# Morpheus_LDO.net
KiCad netlist of a schematic drawn in Altium Designer
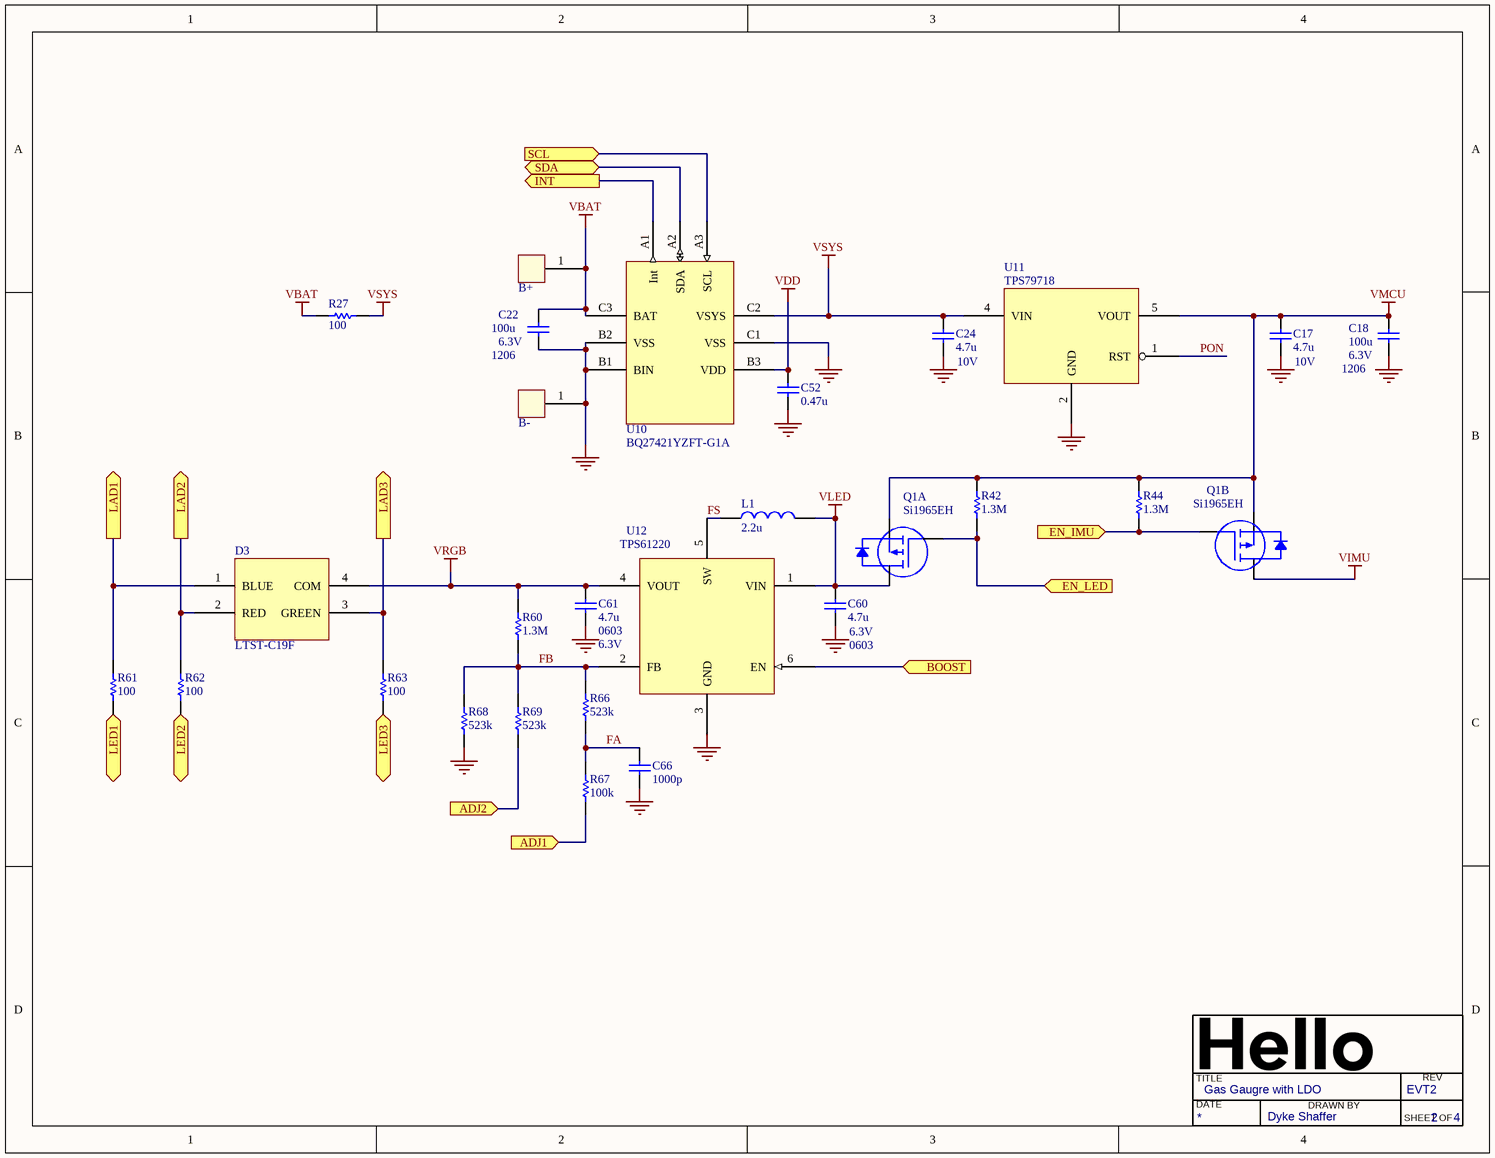
[diagram p0: Morpheus_LDO.SchDoc]

(export (version "E")
  (design (tool "Eeschema 10.0.6"))
  (components
    (comp (ref "B+")
      (value "5016")
      (footprint "TP0875x050")
      (description "Single-pad test point")
      (libsource (lib "Mopd") (part "5016"))
    )
    (comp (ref "B-")
      (value "5016")
      (footprint "TP0875x050")
      (description "Single-pad test point")
      (libsource (lib "Mopd") (part "5016"))
    )
    (comp (ref "C17")
      (value "4.7u")
      (footprint "CAP0402")
      (description "Chip capacitor")
      (fields (field (name "TOLERANCE") "10%") (field (name "VOLTAGE") "10V"))
      (libsource (lib "Hello") (part "C_4.7u_10_10_JB_0402"))
    )
    (comp (ref "C18")
      (value "100u")
      (footprint "CAP1206")
      (description "Chip capacitor")
      (fields (field (name "SIZE") "1206") (field (name "TOLERANCE") "20%") (field (name "VOLTAGE") "6.3V"))
      (libsource (lib "Hello") (part "C_100u_20_6.3_X5R_1206"))
    )
    (comp (ref "C22")
      (value "100u")
      (footprint "CAP1206")
      (description "Chip capacitor")
      (fields (field (name "SIZE") "1206") (field (name "TOLERANCE") "20%") (field (name "VOLTAGE") "6.3V"))
      (libsource (lib "Hello") (part "C_100u_20_6.3_X5R_1206"))
    )
    (comp (ref "C24")
      (value "4.7u")
      (footprint "CAP0402")
      (description "Chip capacitor")
      (fields (field (name "TOLERANCE") "10%") (field (name "VOLTAGE") "10V"))
      (libsource (lib "Hello") (part "C_4.7u_10_10_JB_0402"))
    )
    (comp (ref "C52")
      (value "0.47u")
      (footprint "CAP0402")
      (description "Chip capacitor")
      (fields (field (name "TOLERANCE") "10%") (field (name "VOLTAGE") "10V"))
      (libsource (lib "Hello") (part "C_0.47u_10_10_X5R_0402"))
    )
    (comp (ref "C60")
      (value "4.7u")
      (footprint "CAP0603")
      (description "Chip capacitor")
      (fields (field (name "SIZE") "0603") (field (name "TOLERANCE") "20%") (field (name "VOLTAGE") "6.3V"))
      (libsource (lib "Hello") (part "C_4.7u_20_6.3_X5R_0603"))
    )
    (comp (ref "C61")
      (value "4.7u")
      (footprint "CAP0603")
      (description "Chip capacitor")
      (fields (field (name "SIZE") "0603") (field (name "TOLERANCE") "20%") (field (name "VOLTAGE") "6.3V"))
      (libsource (lib "Hello") (part "C_4.7u_20_6.3_X5R_0603"))
    )
    (comp (ref "C66")
      (value "1000p")
      (footprint "CAP0402")
      (description "Chip capacitor")
      (fields (field (name "TOLERANCE") "10%") (field (name "VOLTAGE") "50V"))
      (libsource (lib "Hello") (part "C_1000p_10_50_X7R_0402"))
    )
    (comp (ref "D3")
      (value "LTST-C19F")
      (footprint "DFN165X210X160X80-4N")
      (description "RGB LED Array")
      (libsource (lib "dykes") (part "LTST-C19F"))
    )
    (comp (ref "L1")
      (value "2.2u")
      (footprint "IND_1206")
      (description "SMD power inductor, 2.2uH")
      (fields (field (name "TOLERANCE") "20%"))
      (libsource (lib "Hello") (part "L_2.2u_1206"))
    )
    (comp (ref "Q1")
      (value "Si1965EH")
      (footprint "SC-70-6")
      (description "Vishay Dual P-Channel MOSFET 1.8v drive 20V 1A")
      (libsource (lib "Hello") (part "Si1965EH"))
    )
    (comp (ref "R27")
      (value "100")
      (footprint "RES0402")
      (description "Chip Resistor")
      (fields (field (name "TOLERANCE") "1 %") (field (name "POWER") "0.1 W"))
      (libsource (lib "Hello") (part "R_100_1_0.1_0402"))
    )
    (comp (ref "R42")
      (value "1.3M")
      (footprint "RES0402")
      (description "Chip Resistor")
      (fields (field (name "TOLERANCE") "5 %") (field (name "POWER") "0.1 W"))
      (libsource (lib "Hello") (part "R_1.3M_5_0.1_0402_1"))
    )
    (comp (ref "R44")
      (value "1.3M")
      (footprint "RES0402")
      (description "Chip Resistor")
      (fields (field (name "TOLERANCE") "5 %") (field (name "POWER") "0.1 W"))
      (libsource (lib "Hello") (part "R_1.3M_5_0.1_0402_1"))
    )
    (comp (ref "R60")
      (value "1.3M")
      (footprint "RES0402")
      (description "Chip Resistor")
      (fields (field (name "TOLERANCE") "5 %") (field (name "POWER") "0.1 W"))
      (libsource (lib "Hello") (part "R_1.3M_5_0.1_0402_1"))
    )
    (comp (ref "R61")
      (value "100")
      (footprint "RES0402")
      (description "Chip Resistor")
      (fields (field (name "TOLERANCE") "1 %") (field (name "POWER") "0.1 W"))
      (libsource (lib "Hello") (part "R_100_1_0.1_0402"))
    )
    (comp (ref "R62")
      (value "100")
      (footprint "RES0402")
      (description "Chip Resistor")
      (fields (field (name "TOLERANCE") "1 %") (field (name "POWER") "0.1 W"))
      (libsource (lib "Hello") (part "R_100_1_0.1_0402"))
    )
    (comp (ref "R63")
      (value "100")
      (footprint "RES0402")
      (description "Chip Resistor")
      (fields (field (name "TOLERANCE") "1 %") (field (name "POWER") "0.1 W"))
      (libsource (lib "Hello") (part "R_100_1_0.1_0402"))
    )
    (comp (ref "R66")
      (value "523k")
      (footprint "RES0402")
      (description "Chip Resistor")
      (fields (field (name "TOLERANCE") "1 %") (field (name "POWER") "0.1 W"))
      (libsource (lib "Hello") (part "R_523k_1_0.1_0402"))
    )
    (comp (ref "R67")
      (value "100k")
      (footprint "RES0402")
      (description "Chip Resistor")
      (fields (field (name "TOLERANCE") "1 %") (field (name "POWER") "0.1 W"))
      (libsource (lib "Hello") (part "R_100k_1_0.1_0402"))
    )
    (comp (ref "R68")
      (value "523k")
      (footprint "RES0402")
      (description "Chip Resistor")
      (fields (field (name "TOLERANCE") "1 %") (field (name "POWER") "0.1 W"))
      (libsource (lib "Hello") (part "R_523k_1_0.1_0402"))
    )
    (comp (ref "R69")
      (value "523k")
      (footprint "RES0402")
      (description "Chip Resistor")
      (fields (field (name "TOLERANCE") "1 %") (field (name "POWER") "0.1 W"))
      (libsource (lib "Hello") (part "R_523k_1_0.1_0402"))
    )
    (comp (ref "U10")
      (value "BQ27421YZFT-G1A")
      (footprint "BGA9C50P3X3_158X162X62")
      (description "TI Fuel Gauge With Integrated Sense Resistor")
      (libsource (lib "Mopd") (part "BQ27421"))
    )
    (comp (ref "U11")
      (value "TPS79718")
      (footprint "SOT65P212X110-5N")
      (description "LDO 1.8V SC70-5")
      (libsource (lib "dykes") (part "TPS79718DCK"))
    )
    (comp (ref "U12")
      (value "TPS61220")
      (footprint "SOT65P212X110-6N")
      (description "Boost Converter")
      (libsource (lib "dykes") (part "TPS61220"))
    )
  )
  (nets
    (net (code "1") (name "/ADJ1") (class "Default")
      (node (ref "R67") (pin "1") (pinfunction "1_1") (pintype "passive"))
    )
    (net (code "2") (name "/ADJ2") (class "Default")
      (node (ref "R69") (pin "1") (pinfunction "1_1") (pintype "passive"))
    )
    (net (code "3") (name "/BOOST") (class "Default")
      (node (ref "U12") (pin "6") (pinfunction "EN_6") (pintype "input"))
    )
    (net (code "4") (name "/EN_IMU") (class "Default")
      (node (ref "Q1") (pin "5") (pinfunction "G2_5") (pintype "passive"))
      (node (ref "R44") (pin "1") (pinfunction "1_1") (pintype "passive"))
    )
    (net (code "5") (name "/EN_LED") (class "Default")
      (node (ref "Q1") (pin "2") (pinfunction "G1_2") (pintype "passive"))
      (node (ref "R42") (pin "1") (pinfunction "1_1") (pintype "passive"))
    )
    (net (code "6") (name "/FA") (class "Default")
      (node (ref "C66") (pin "2") (pinfunction "2_2") (pintype "passive"))
      (node (ref "R66") (pin "1") (pinfunction "1_1") (pintype "passive"))
      (node (ref "R67") (pin "2") (pinfunction "2_2") (pintype "passive"))
    )
    (net (code "7") (name "/FB") (class "Default")
      (node (ref "R60") (pin "1") (pinfunction "1_1") (pintype "passive"))
      (node (ref "R66") (pin "2") (pinfunction "2_2") (pintype "passive"))
      (node (ref "R68") (pin "2") (pinfunction "2_2") (pintype "passive"))
      (node (ref "R69") (pin "2") (pinfunction "2_2") (pintype "passive"))
      (node (ref "U12") (pin "2") (pinfunction "FB_2") (pintype "passive"))
    )
    (net (code "8") (name "/FS") (class "Default")
      (node (ref "L1") (pin "2") (pintype "passive"))
      (node (ref "U12") (pin "5") (pinfunction "SW_5") (pintype "passive"))
    )
    (net (code "9") (name "/INT") (class "Default")
      (node (ref "U10") (pin "A1") (pinfunction "Int_A1") (pintype "output"))
    )
    (net (code "10") (name "/LAD1") (class "Default")
      (node (ref "D3") (pin "1") (pinfunction "BLUE_1") (pintype "passive"))
      (node (ref "R61") (pin "2") (pinfunction "2_2") (pintype "passive"))
    )
    (net (code "11") (name "/LAD2") (class "Default")
      (node (ref "D3") (pin "2") (pinfunction "RED_2") (pintype "passive"))
      (node (ref "R62") (pin "2") (pinfunction "2_2") (pintype "passive"))
    )
    (net (code "12") (name "/LAD3") (class "Default")
      (node (ref "D3") (pin "3") (pinfunction "GREEN_3") (pintype "passive"))
      (node (ref "R63") (pin "2") (pinfunction "2_2") (pintype "passive"))
    )
    (net (code "13") (name "/LED1") (class "Default")
      (node (ref "R61") (pin "1") (pinfunction "1_1") (pintype "passive"))
    )
    (net (code "14") (name "/LED2") (class "Default")
      (node (ref "R62") (pin "1") (pinfunction "1_1") (pintype "passive"))
    )
    (net (code "15") (name "/LED3") (class "Default")
      (node (ref "R63") (pin "1") (pinfunction "1_1") (pintype "passive"))
    )
    (net (code "16") (name "/PON") (class "Default")
      (node (ref "U11") (pin "1") (pinfunction "RST_1") (pintype "open_collector"))
    )
    (net (code "17") (name "/SCL") (class "Default")
      (node (ref "U10") (pin "A3") (pinfunction "SCL_A3") (pintype "input"))
    )
    (net (code "18") (name "/SDA") (class "Default")
      (node (ref "U10") (pin "A2") (pinfunction "SDA_A2") (pintype "bidirectional"))
    )
    (net (code "19") (name "GND") (class "Default")
      (node (ref "B-") (pin "1") (pinfunction "1_1") (pintype "passive"))
      (node (ref "C17") (pin "1") (pinfunction "1_1") (pintype "passive"))
      (node (ref "C18") (pin "1") (pinfunction "1_1") (pintype "passive"))
      (node (ref "C22") (pin "2") (pinfunction "2_2") (pintype "passive"))
      (node (ref "C24") (pin "1") (pinfunction "1_1") (pintype "passive"))
      (node (ref "C52") (pin "2") (pinfunction "2_2") (pintype "passive"))
      (node (ref "C60") (pin "1") (pinfunction "1_1") (pintype "passive"))
      (node (ref "C61") (pin "1") (pinfunction "1_1") (pintype "passive"))
      (node (ref "C66") (pin "1") (pinfunction "1_1") (pintype "passive"))
      (node (ref "R68") (pin "1") (pinfunction "1_1") (pintype "passive"))
      (node (ref "U10") (pin "B1") (pinfunction "BIN_B1") (pintype "power_in"))
      (node (ref "U10") (pin "B2") (pinfunction "VSS_B2") (pintype "power_in"))
      (node (ref "U10") (pin "C1") (pinfunction "VSS_C1") (pintype "power_in"))
      (node (ref "U11") (pin "2") (pinfunction "GND_2") (pintype "power_in"))
      (node (ref "U12") (pin "3") (pinfunction "GND_3") (pintype "power_in"))
    )
    (net (code "20") (name "VBAT") (class "Default")
      (node (ref "B+") (pin "1") (pinfunction "1_1") (pintype "passive"))
      (node (ref "C22") (pin "1") (pinfunction "1_1") (pintype "passive"))
      (node (ref "R27") (pin "2") (pinfunction "2_2") (pintype "passive"))
      (node (ref "U10") (pin "C3") (pinfunction "BAT_C3") (pintype "power_in"))
    )
    (net (code "21") (name "VDD") (class "Default")
      (node (ref "C52") (pin "1") (pinfunction "1_1") (pintype "passive"))
      (node (ref "U10") (pin "B3") (pinfunction "VDD_B3") (pintype "power_in"))
    )
    (net (code "22") (name "VIMU") (class "Default")
      (node (ref "Q1") (pin "3") (pinfunction "D2_3") (pintype "passive"))
    )
    (net (code "23") (name "VLED") (class "Default")
      (node (ref "C60") (pin "2") (pinfunction "2_2") (pintype "passive"))
      (node (ref "L1") (pin "1") (pintype "passive"))
      (node (ref "Q1") (pin "6") (pinfunction "D1_6") (pintype "passive"))
      (node (ref "U12") (pin "1") (pinfunction "VIN_1") (pintype "power_in"))
    )
    (net (code "24") (name "VMCU") (class "Default")
      (node (ref "C17") (pin "2") (pinfunction "2_2") (pintype "passive"))
      (node (ref "C18") (pin "2") (pinfunction "2_2") (pintype "passive"))
      (node (ref "Q1") (pin "1") (pinfunction "S1_1") (pintype "passive"))
      (node (ref "Q1") (pin "4") (pinfunction "S2_4") (pintype "passive"))
      (node (ref "R42") (pin "2") (pinfunction "2_2") (pintype "passive"))
      (node (ref "R44") (pin "2") (pinfunction "2_2") (pintype "passive"))
      (node (ref "U11") (pin "5") (pinfunction "VOUT_5") (pintype "power_in"))
    )
    (net (code "25") (name "VRGB") (class "Default")
      (node (ref "C61") (pin "2") (pinfunction "2_2") (pintype "passive"))
      (node (ref "D3") (pin "4") (pinfunction "COM_4") (pintype "passive"))
      (node (ref "R60") (pin "2") (pinfunction "2_2") (pintype "passive"))
      (node (ref "U12") (pin "4") (pinfunction "VOUT_4") (pintype "power_in"))
    )
    (net (code "26") (name "VSYS") (class "Default")
      (node (ref "C24") (pin "2") (pinfunction "2_2") (pintype "passive"))
      (node (ref "R27") (pin "1") (pinfunction "1_1") (pintype "passive"))
      (node (ref "U10") (pin "C2") (pinfunction "VSYS_C2") (pintype "power_in"))
      (node (ref "U11") (pin "4") (pinfunction "VIN_4") (pintype "power_in"))
    )
  )
)
